# motherboard.net
KiCad netlist of a schematic drawn in EAGLE
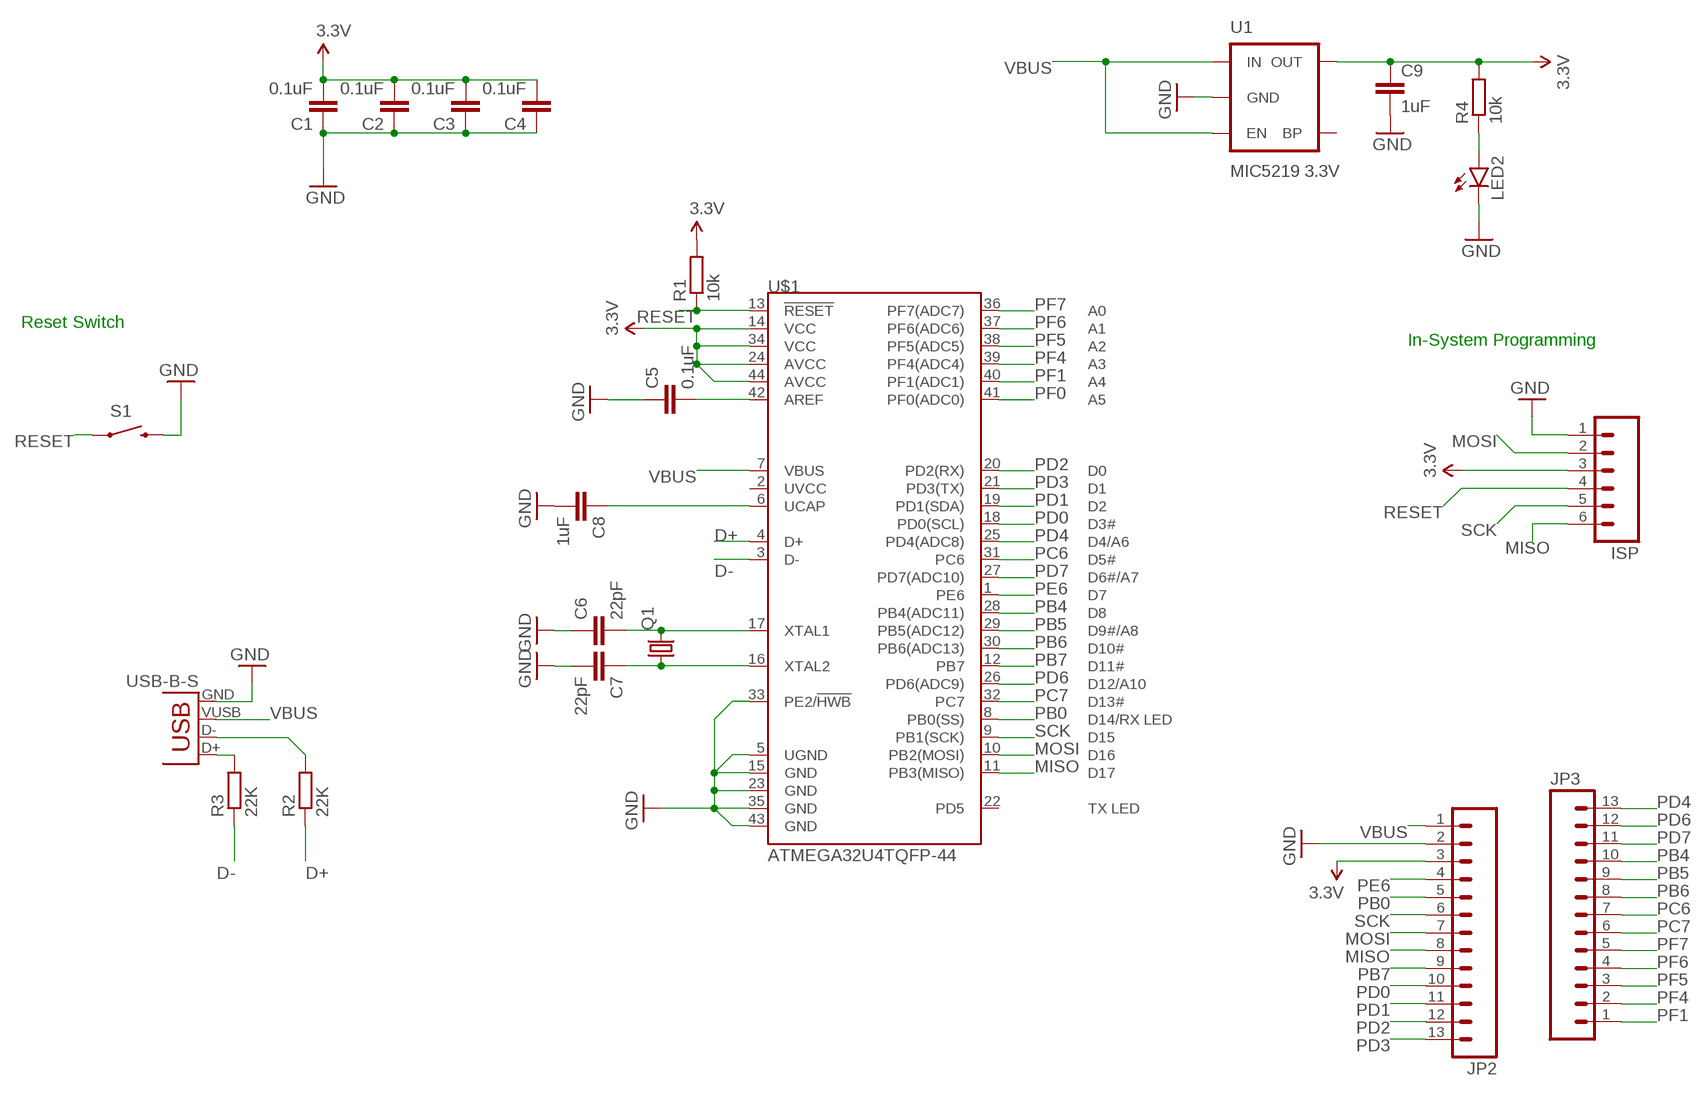
[diagram p0: schematic, sheet 1]

(export (version "E")
  (design (tool "Eeschema 10.0.6"))
  (components
    (comp (ref "C1")
      (value "0.1uF")
      (footprint "eagle-import:C0805")
      (libsource (lib "eagle-import") (part "C0805"))
    )
    (comp (ref "C2")
      (value "0.1uF")
      (footprint "eagle-import:C0805")
      (libsource (lib "eagle-import") (part "C0805"))
    )
    (comp (ref "C3")
      (value "0.1uF")
      (footprint "eagle-import:C0805")
      (libsource (lib "eagle-import") (part "C0805"))
    )
    (comp (ref "C4")
      (value "0.1uF")
      (footprint "eagle-import:C0805")
      (libsource (lib "eagle-import") (part "C0805"))
    )
    (comp (ref "C5")
      (value "0.1uF")
      (footprint "eagle-import:C0805")
      (libsource (lib "eagle-import") (part "C0805"))
    )
    (comp (ref "C6")
      (value "22pF")
      (footprint "eagle-import:C0805")
      (libsource (lib "eagle-import") (part "C0805"))
    )
    (comp (ref "C7")
      (value "22pF")
      (footprint "eagle-import:C0805")
      (libsource (lib "eagle-import") (part "C0805"))
    )
    (comp (ref "C8")
      (value "1uF")
      (footprint "eagle-import:C0805")
      (libsource (lib "eagle-import") (part "C0805"))
    )
    (comp (ref "C9")
      (value "1uF")
      (footprint "eagle-import:C0805")
      (libsource (lib "eagle-import") (part "C0805"))
    )
    (comp (ref "ISP")
      (value "M06SMD")
      (footprint "eagle-import:1X06-SMD")
      (libsource (lib "eagle-import") (part "M06SMD"))
    )
    (comp (ref "JP1")
      (value "USB-B-S")
      (footprint "eagle-import:USB-B-SMT")
      (libsource (lib "eagle-import") (part "USB-B-S"))
    )
    (comp (ref "JP2")
      (value "M13")
      (footprint "eagle-import:1X13")
      (libsource (lib "eagle-import") (part "M13"))
    )
    (comp (ref "JP3")
      (value "M13")
      (footprint "eagle-import:1X13")
      (libsource (lib "eagle-import") (part "M13"))
    )
    (comp (ref "LED2")
      (value "LED1206")
      (footprint "eagle-import:LED-1206")
      (libsource (lib "eagle-import") (part "LED1206"))
    )
    (comp (ref "Q1")
      (value "CRYSTALHC49S")
      (footprint "eagle-import:HC49_S")
      (libsource (lib "eagle-import") (part "CRYSTALHC49S"))
    )
    (comp (ref "R1")
      (value "10k")
      (footprint "eagle-import:R0805")
      (libsource (lib "eagle-import") (part "R0805"))
    )
    (comp (ref "R2")
      (value "22K")
      (footprint "eagle-import:R0805")
      (libsource (lib "eagle-import") (part "R0805"))
    )
    (comp (ref "R3")
      (value "22K")
      (footprint "eagle-import:R0805")
      (libsource (lib "eagle-import") (part "R0805"))
    )
    (comp (ref "R4")
      (value "10k")
      (footprint "eagle-import:R0805")
      (libsource (lib "eagle-import") (part "R0805"))
    )
    (comp (ref "S1")
      (value "SWITCH-MOMENTARY-2PTH")
      (footprint "eagle-import:TACTILE-PTH")
      (libsource (lib "eagle-import") (part "SWITCH-MOMENTARY-2PTH"))
    )
    (comp (ref "U$1")
      (value "ATMEGA32U4TQFP-44")
      (footprint "eagle-import:TQFP44")
      (libsource (lib "eagle-import") (part "ATMEGA32U4TQFP-44"))
    )
    (comp (ref "U1")
      (value "MIC5219 3.3V")
      (footprint "eagle-import:SOT23-5")
      (libsource (lib "eagle-import") (part "V_REG_MIC52193.3V"))
    )
  )
  (nets
    (net (code "1") (name "/D+") (class "Default")
      (node (ref "R2") (pin "1") (pinfunction "1_1") (pintype "passive"))
      (node (ref "U$1") (pin "4") (pinfunction "D+_4") (pintype "bidirectional"))
    )
    (net (code "2") (name "/D-") (class "Default")
      (node (ref "R3") (pin "1") (pinfunction "1_1") (pintype "passive"))
      (node (ref "U$1") (pin "3") (pinfunction "D-_3") (pintype "bidirectional"))
    )
    (net (code "3") (name "/MISO") (class "Default")
      (node (ref "ISP") (pin "6") (pinfunction "6_6") (pintype "passive"))
      (node (ref "JP2") (pin "8") (pinfunction "8_8") (pintype "passive"))
      (node (ref "U$1") (pin "11") (pinfunction "PB3(MISO)_11") (pintype "bidirectional"))
    )
    (net (code "4") (name "/MOSI") (class "Default")
      (node (ref "ISP") (pin "2") (pinfunction "2_2") (pintype "passive"))
      (node (ref "JP2") (pin "7") (pinfunction "7_7") (pintype "passive"))
      (node (ref "U$1") (pin "10") (pinfunction "PB2(MOSI)_10") (pintype "bidirectional"))
    )
    (net (code "5") (name "/PB0") (class "Default")
      (node (ref "JP2") (pin "5") (pinfunction "5_5") (pintype "passive"))
      (node (ref "U$1") (pin "8") (pinfunction "PB0(SS)_8") (pintype "bidirectional"))
    )
    (net (code "6") (name "/PB4") (class "Default")
      (node (ref "JP3") (pin "10") (pinfunction "10_10") (pintype "passive"))
      (node (ref "U$1") (pin "28") (pinfunction "PB4(ADC11)_28") (pintype "bidirectional"))
    )
    (net (code "7") (name "/PB5") (class "Default")
      (node (ref "JP3") (pin "9") (pinfunction "9_9") (pintype "passive"))
      (node (ref "U$1") (pin "29") (pinfunction "PB5(ADC12)_29") (pintype "bidirectional"))
    )
    (net (code "8") (name "/PB6") (class "Default")
      (node (ref "JP3") (pin "8") (pinfunction "8_8") (pintype "passive"))
      (node (ref "U$1") (pin "30") (pinfunction "PB6(ADC13)_30") (pintype "bidirectional"))
    )
    (net (code "9") (name "/PB7") (class "Default")
      (node (ref "JP2") (pin "9") (pinfunction "9_9") (pintype "passive"))
      (node (ref "U$1") (pin "12") (pinfunction "PB7_12") (pintype "bidirectional"))
    )
    (net (code "10") (name "/PC6") (class "Default")
      (node (ref "JP3") (pin "7") (pinfunction "7_7") (pintype "passive"))
      (node (ref "U$1") (pin "31") (pinfunction "PC6_31") (pintype "bidirectional"))
    )
    (net (code "11") (name "/PC7") (class "Default")
      (node (ref "JP3") (pin "6") (pinfunction "6_6") (pintype "passive"))
      (node (ref "U$1") (pin "32") (pinfunction "PC7_32") (pintype "bidirectional"))
    )
    (net (code "12") (name "/PD0") (class "Default")
      (node (ref "JP2") (pin "10") (pinfunction "10_10") (pintype "passive"))
      (node (ref "U$1") (pin "18") (pinfunction "PD0(SCL)_18") (pintype "bidirectional"))
    )
    (net (code "13") (name "/PD1") (class "Default")
      (node (ref "JP2") (pin "11") (pinfunction "11_11") (pintype "passive"))
      (node (ref "U$1") (pin "19") (pinfunction "PD1(SDA)_19") (pintype "bidirectional"))
    )
    (net (code "14") (name "/PD2") (class "Default")
      (node (ref "JP2") (pin "12") (pinfunction "12_12") (pintype "passive"))
      (node (ref "U$1") (pin "20") (pinfunction "PD2(RX)_20") (pintype "bidirectional"))
    )
    (net (code "15") (name "/PD3") (class "Default")
      (node (ref "JP2") (pin "13") (pinfunction "13_13") (pintype "passive"))
      (node (ref "U$1") (pin "21") (pinfunction "PD3(TX)_21") (pintype "bidirectional"))
    )
    (net (code "16") (name "/PD4") (class "Default")
      (node (ref "JP3") (pin "13") (pinfunction "13_13") (pintype "passive"))
      (node (ref "U$1") (pin "25") (pinfunction "PD4(ADC8)_25") (pintype "bidirectional"))
    )
    (net (code "17") (name "/PD6") (class "Default")
      (node (ref "JP3") (pin "12") (pinfunction "12_12") (pintype "passive"))
      (node (ref "U$1") (pin "26") (pinfunction "PD6(ADC9)_26") (pintype "bidirectional"))
    )
    (net (code "18") (name "/PD7") (class "Default")
      (node (ref "JP3") (pin "11") (pinfunction "11_11") (pintype "passive"))
      (node (ref "U$1") (pin "27") (pinfunction "PD7(ADC10)_27") (pintype "bidirectional"))
    )
    (net (code "19") (name "/PE6") (class "Default")
      (node (ref "JP2") (pin "4") (pinfunction "4_4") (pintype "passive"))
      (node (ref "U$1") (pin "1") (pinfunction "PE6_1") (pintype "bidirectional"))
    )
    (net (code "20") (name "/PF0") (class "Default")
      (node (ref "U$1") (pin "41") (pinfunction "PF0(ADC0)_41") (pintype "bidirectional"))
    )
    (net (code "21") (name "/PF1") (class "Default")
      (node (ref "JP3") (pin "1") (pinfunction "1_1") (pintype "passive"))
      (node (ref "U$1") (pin "40") (pinfunction "PF1(ADC1)_40") (pintype "bidirectional"))
    )
    (net (code "22") (name "/PF4") (class "Default")
      (node (ref "JP3") (pin "2") (pinfunction "2_2") (pintype "passive"))
      (node (ref "U$1") (pin "39") (pinfunction "PF4(ADC4)_39") (pintype "bidirectional"))
    )
    (net (code "23") (name "/PF5") (class "Default")
      (node (ref "JP3") (pin "3") (pinfunction "3_3") (pintype "passive"))
      (node (ref "U$1") (pin "38") (pinfunction "PF5(ADC5)_38") (pintype "bidirectional"))
    )
    (net (code "24") (name "/PF6") (class "Default")
      (node (ref "JP3") (pin "4") (pinfunction "4_4") (pintype "passive"))
      (node (ref "U$1") (pin "37") (pinfunction "PF6(ADC6)_37") (pintype "bidirectional"))
    )
    (net (code "25") (name "/PF7") (class "Default")
      (node (ref "JP3") (pin "5") (pinfunction "5_5") (pintype "passive"))
      (node (ref "U$1") (pin "36") (pinfunction "PF7(ADC7)_36") (pintype "bidirectional"))
    )
    (net (code "26") (name "/RESET") (class "Default")
      (node (ref "ISP") (pin "4") (pinfunction "4_4") (pintype "passive"))
      (node (ref "R1") (pin "1") (pinfunction "1_1") (pintype "passive"))
      (node (ref "S1") (pin "1") (pinfunction "1_1") (pintype "passive"))
      (node (ref "U$1") (pin "13") (pinfunction "~{RESET}_13") (pintype "bidirectional"))
    )
    (net (code "27") (name "/SCK") (class "Default")
      (node (ref "ISP") (pin "5") (pinfunction "5_5") (pintype "passive"))
      (node (ref "JP2") (pin "6") (pinfunction "6_6") (pintype "passive"))
      (node (ref "U$1") (pin "9") (pinfunction "PB1(SCK)_9") (pintype "bidirectional"))
    )
    (net (code "28") (name "/VBUS") (class "Default")
      (node (ref "JP1") (pin "VUSB") (pinfunction "VBUS_VUSB") (pintype "bidirectional"))
      (node (ref "JP2") (pin "1") (pinfunction "1_1") (pintype "passive"))
      (node (ref "U$1") (pin "7") (pinfunction "VBUS_7") (pintype "bidirectional"))
      (node (ref "U1") (pin "1") (pinfunction "IN_1") (pintype "input"))
      (node (ref "U1") (pin "3") (pinfunction "EN_3") (pintype "input"))
    )
    (net (code "29") (name "3.3V") (class "Default")
      (node (ref "C1") (pin "2") (pinfunction "2_2") (pintype "passive"))
      (node (ref "C2") (pin "2") (pinfunction "2_2") (pintype "passive"))
      (node (ref "C3") (pin "2") (pinfunction "2_2") (pintype "passive"))
      (node (ref "C4") (pin "2") (pinfunction "2_2") (pintype "passive"))
      (node (ref "C9") (pin "1") (pinfunction "1_1") (pintype "passive"))
      (node (ref "ISP") (pin "3") (pinfunction "3_3") (pintype "passive"))
      (node (ref "JP2") (pin "3") (pinfunction "3_3") (pintype "passive"))
      (node (ref "R1") (pin "2") (pinfunction "2_2") (pintype "passive"))
      (node (ref "R4") (pin "2") (pinfunction "2_2") (pintype "passive"))
      (node (ref "U$1") (pin "14") (pinfunction "VCC_14") (pintype "bidirectional"))
      (node (ref "U$1") (pin "24") (pinfunction "AVCC_24") (pintype "bidirectional"))
      (node (ref "U$1") (pin "34") (pinfunction "VCC_34") (pintype "bidirectional"))
      (node (ref "U$1") (pin "44") (pinfunction "AVCC_44") (pintype "bidirectional"))
      (node (ref "U1") (pin "5") (pinfunction "OUT_5") (pintype "passive"))
    )
    (net (code "30") (name "GND") (class "Default")
      (node (ref "C1") (pin "1") (pinfunction "1_1") (pintype "passive"))
      (node (ref "C2") (pin "1") (pinfunction "1_1") (pintype "passive"))
      (node (ref "C3") (pin "1") (pinfunction "1_1") (pintype "passive"))
      (node (ref "C4") (pin "1") (pinfunction "1_1") (pintype "passive"))
      (node (ref "C5") (pin "1") (pinfunction "1_1") (pintype "passive"))
      (node (ref "C6") (pin "1") (pinfunction "1_1") (pintype "passive"))
      (node (ref "C7") (pin "2") (pinfunction "2_2") (pintype "passive"))
      (node (ref "C8") (pin "2") (pinfunction "2_2") (pintype "passive"))
      (node (ref "C9") (pin "2") (pinfunction "2_2") (pintype "passive"))
      (node (ref "ISP") (pin "1") (pinfunction "1_1") (pintype "passive"))
      (node (ref "JP1") (pin "GND") (pinfunction "GND_GND") (pintype "bidirectional"))
      (node (ref "JP2") (pin "2") (pinfunction "2_2") (pintype "passive"))
      (node (ref "LED2") (pin "C") (pinfunction "C_C") (pintype "passive"))
      (node (ref "S1") (pin "3") (pinfunction "2_3") (pintype "passive"))
      (node (ref "U$1") (pin "15") (pinfunction "GND_15") (pintype "bidirectional"))
      (node (ref "U$1") (pin "23") (pinfunction "GND_23") (pintype "bidirectional"))
      (node (ref "U$1") (pin "33") (pinfunction "PE2/~{HWB}_33") (pintype "bidirectional"))
      (node (ref "U$1") (pin "35") (pinfunction "GND_35") (pintype "bidirectional"))
      (node (ref "U$1") (pin "43") (pinfunction "GND_43") (pintype "bidirectional"))
      (node (ref "U$1") (pin "5") (pinfunction "UGND_5") (pintype "bidirectional"))
      (node (ref "U1") (pin "2") (pinfunction "GND_2") (pintype "input"))
    )
    (net (code "31") (name "Net-(JP1-PadD+)") (class "Default")
      (node (ref "JP1") (pin "D+") (pinfunction "D+_D+") (pintype "bidirectional"))
      (node (ref "R3") (pin "2") (pinfunction "2_2") (pintype "passive"))
    )
    (net (code "32") (name "Net-(JP1-PadD-)") (class "Default")
      (node (ref "JP1") (pin "D-") (pinfunction "D-_D-") (pintype "bidirectional"))
      (node (ref "R2") (pin "2") (pinfunction "2_2") (pintype "passive"))
    )
    (net (code "33") (name "Net-(LED2-PadA)") (class "Default")
      (node (ref "LED2") (pin "A") (pinfunction "A_A") (pintype "passive"))
      (node (ref "R4") (pin "1") (pinfunction "1_1") (pintype "passive"))
    )
    (net (code "34") (name "Net-(U$1-AREF)") (class "Default")
      (node (ref "C5") (pin "2") (pinfunction "2_2") (pintype "passive"))
      (node (ref "U$1") (pin "42") (pinfunction "AREF_42") (pintype "bidirectional"))
    )
    (net (code "35") (name "Net-(U$1-UCAP)") (class "Default")
      (node (ref "C8") (pin "1") (pinfunction "1_1") (pintype "passive"))
      (node (ref "U$1") (pin "6") (pinfunction "UCAP_6") (pintype "bidirectional"))
    )
    (net (code "36") (name "Net-(U$1-XTAL1)") (class "Default")
      (node (ref "C6") (pin "2") (pinfunction "2_2") (pintype "passive"))
      (node (ref "Q1") (pin "2") (pinfunction "2_2") (pintype "passive"))
      (node (ref "U$1") (pin "17") (pinfunction "XTAL1_17") (pintype "bidirectional"))
    )
    (net (code "37") (name "Net-(U$1-XTAL2)") (class "Default")
      (node (ref "C7") (pin "1") (pinfunction "1_1") (pintype "passive"))
      (node (ref "Q1") (pin "1") (pinfunction "1_1") (pintype "passive"))
      (node (ref "U$1") (pin "16") (pinfunction "XTAL2_16") (pintype "bidirectional"))
    )
    (net (code "38") (name "unconnected-(U$1-PD5-Pad22)") (class "Default")
      (node (ref "U$1") (pin "22") (pinfunction "PD5_22") (pintype "bidirectional"))
    )
    (net (code "39") (name "unconnected-(U$1-UVCC-Pad2)") (class "Default")
      (node (ref "U$1") (pin "2") (pinfunction "UVCC_2") (pintype "bidirectional"))
    )
    (net (code "40") (name "unconnected-(U1-BP-Pad4)") (class "Default")
      (node (ref "U1") (pin "4") (pinfunction "BP_4") (pintype "input"))
    )
  )
)
